# agv_drv.net
KiCad netlist of a schematic drawn in Altium Designer
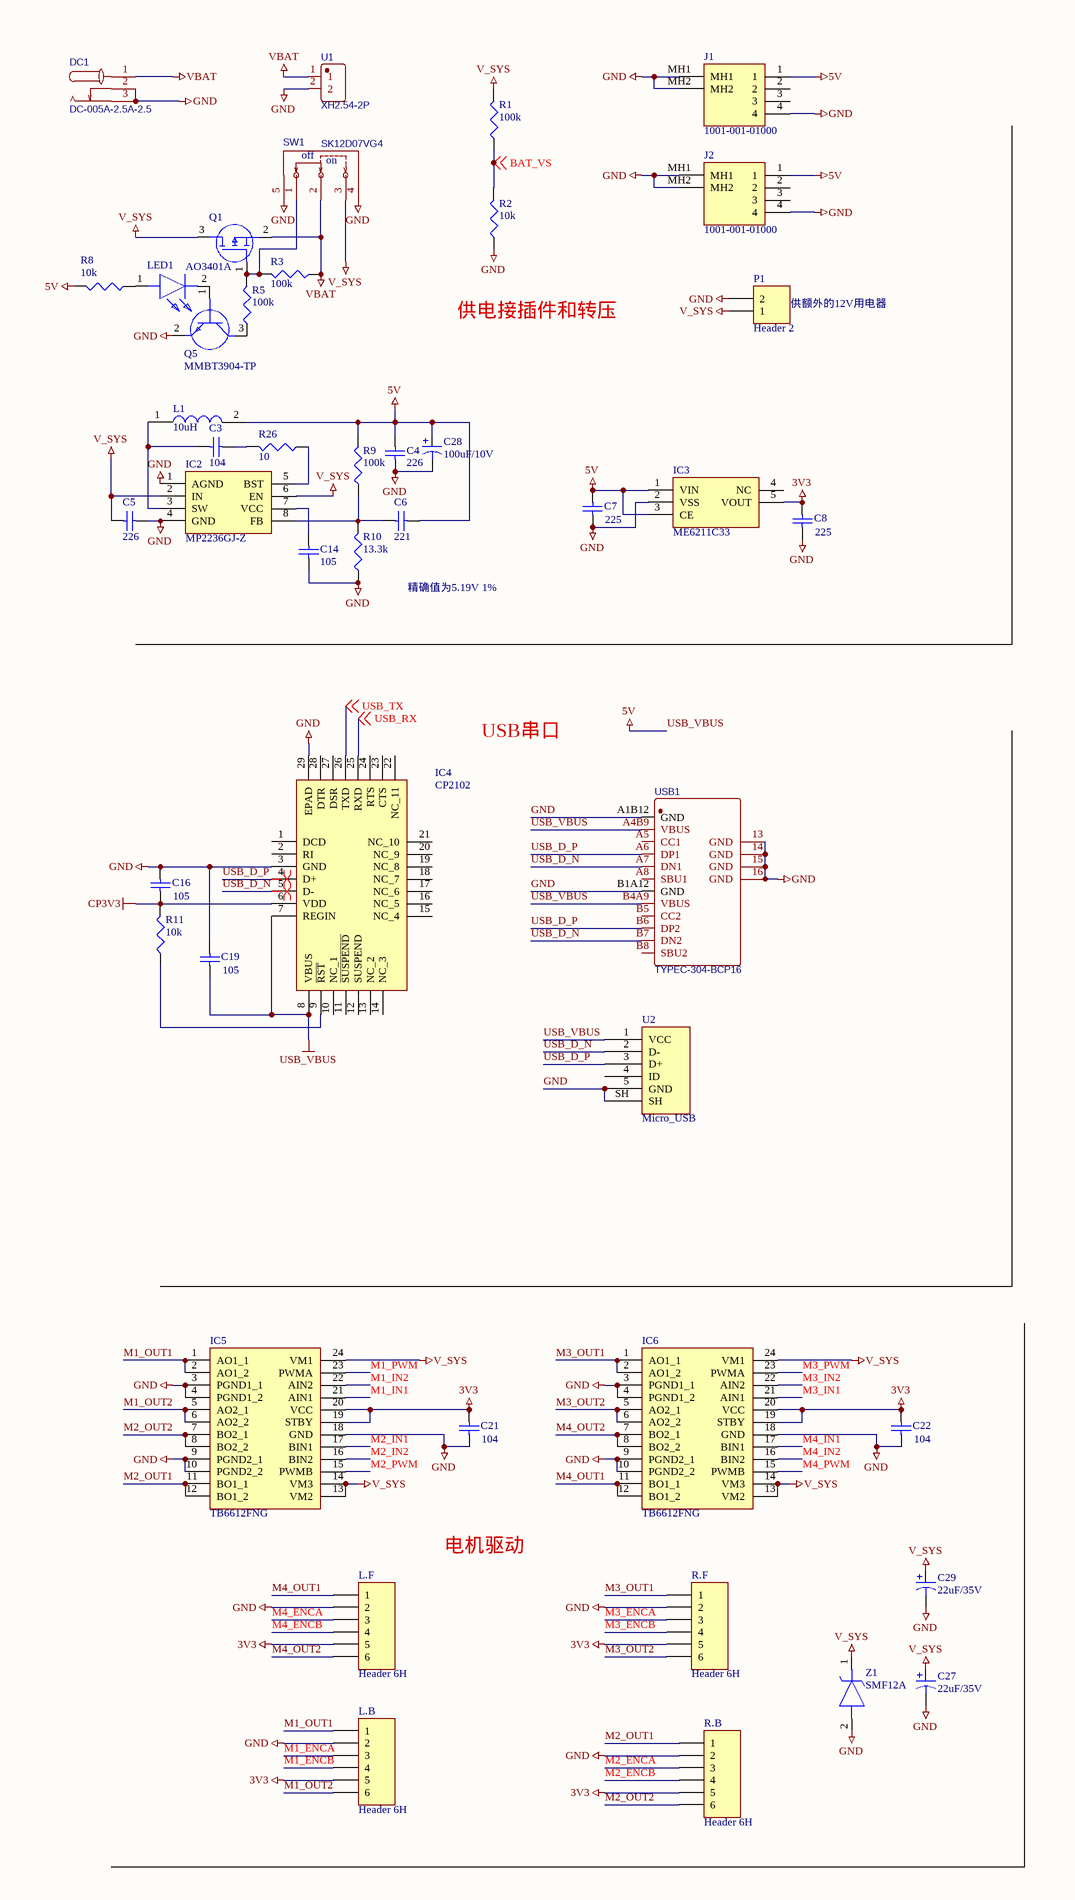
[diagram p0: agv_drv.SchDoc, left]
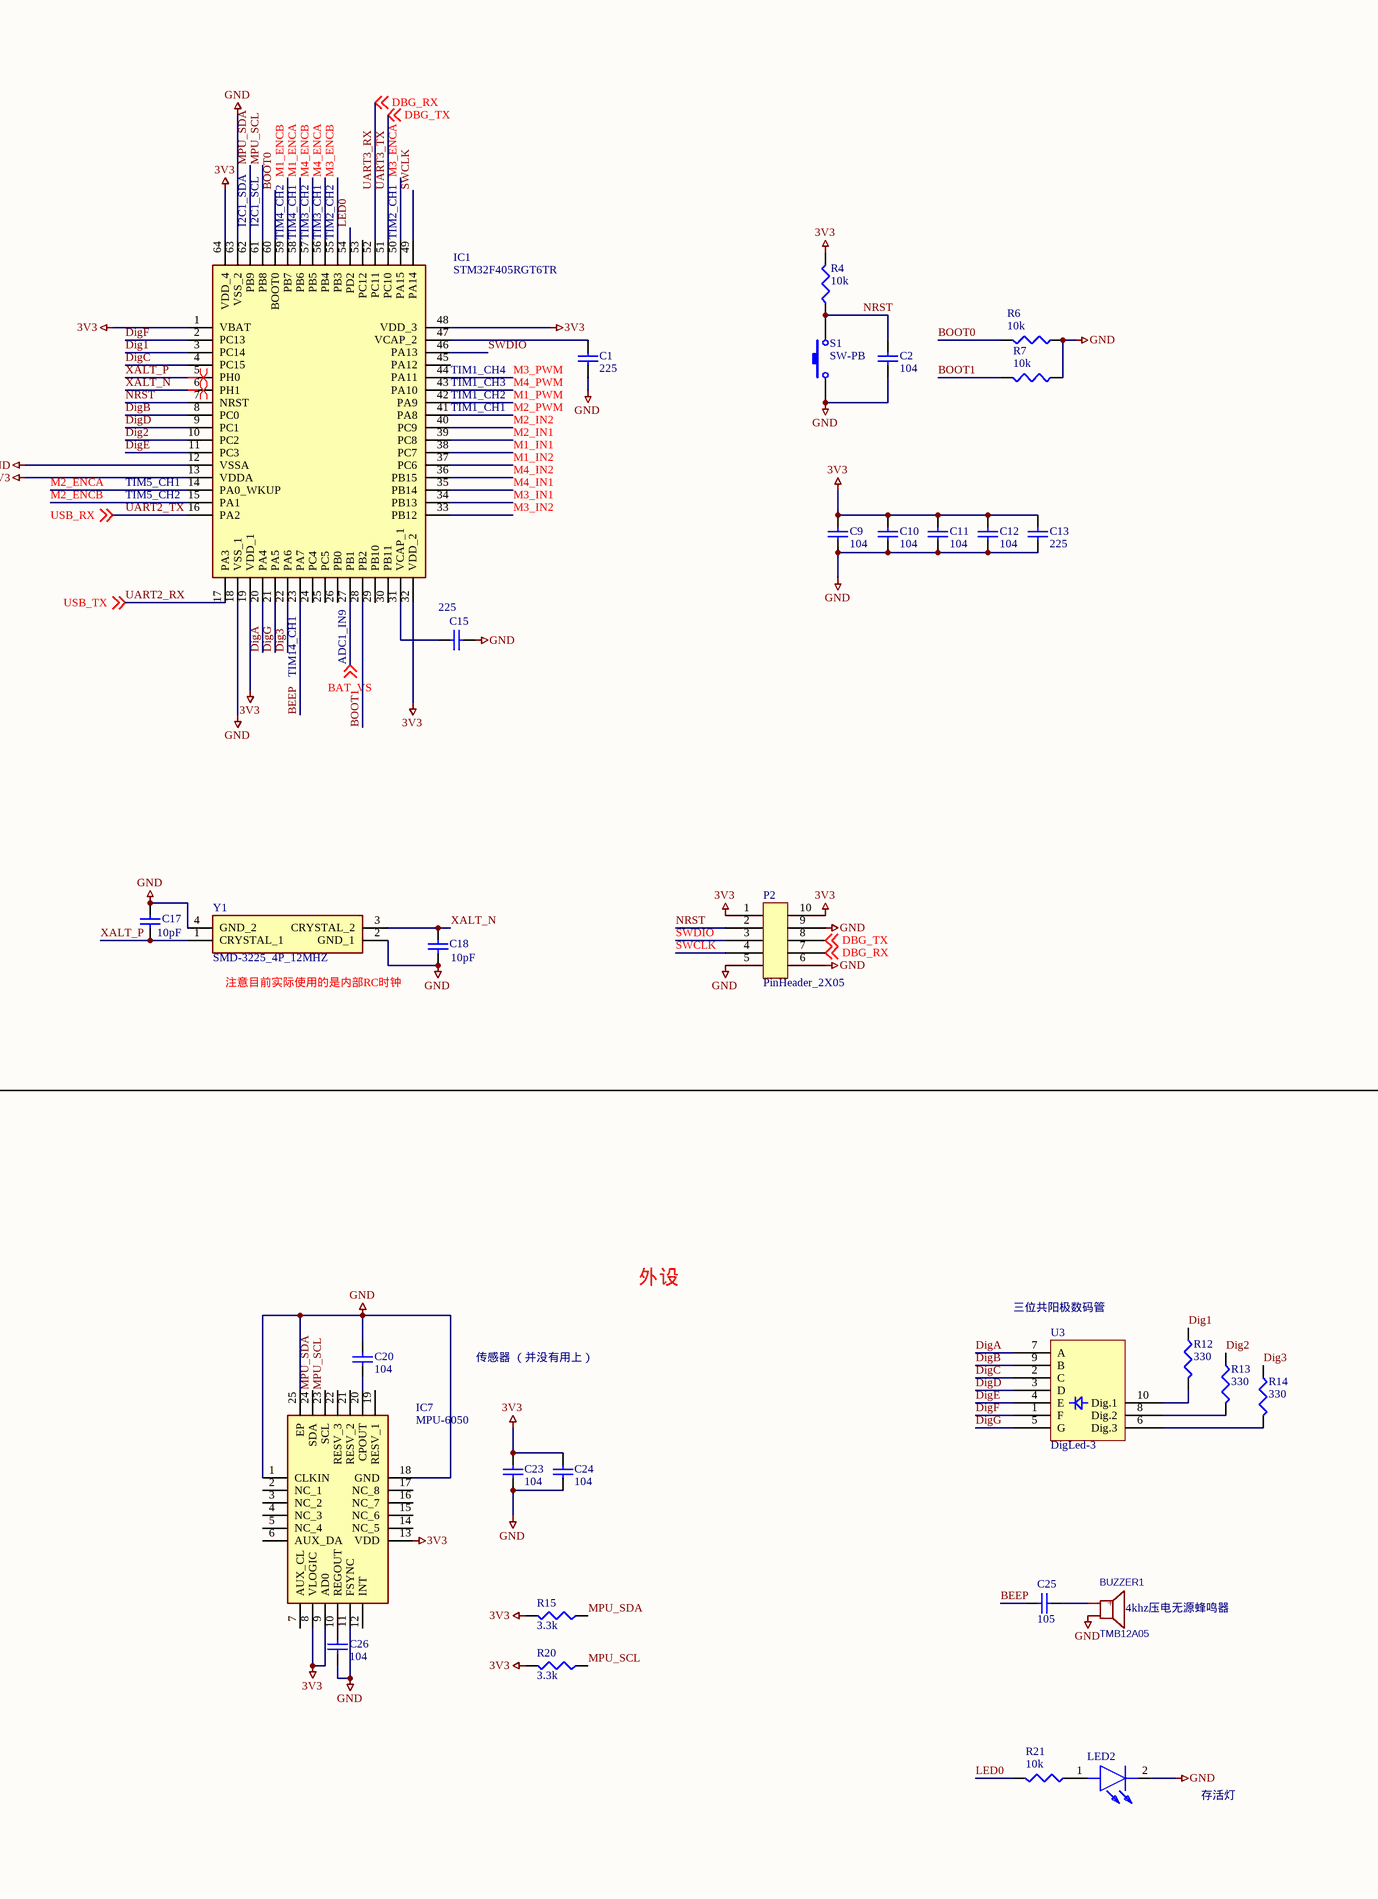
[diagram p1: agv_drv.SchDoc, right]

(export (version "E")
  (design (tool "Eeschema 10.0.6"))
  (components
    (comp (ref "BUZZER1")
      (value "TMB12A05")
      (footprint "BUZ-TH_BD12.5-P6.50-D0.8-FD")
      (fields (field (name "BOM_SUPPLIER PART") "C96093"))
      (libsource (lib "SamacSys") (part "TMB12A05"))
    )
    (comp (ref "C1")
      (value "225")
      (footprint "1608[0603]")
      (description "Capacitor (Semiconductor SIM Model)")
      (fields (field (name "PUBLISHER") "Altium Limited"))
      (libsource (lib "Miscellaneous Devices") (part "Cap Semi"))
    )
    (comp (ref "C2")
      (value "104")
      (footprint "1608[0603]")
      (description "Capacitor (Semiconductor SIM Model)")
      (fields (field (name "PUBLISHER") "Altium Limited"))
      (libsource (lib "Miscellaneous Devices") (part "Cap Semi"))
    )
    (comp (ref "C3")
      (value "104")
      (footprint "1608[0603]")
      (description "Capacitor (Semiconductor SIM Model)")
      (fields (field (name "PUBLISHER") "Altium Limited"))
      (libsource (lib "Miscellaneous Devices") (part "Cap Semi"))
    )
    (comp (ref "C4")
      (value "226")
      (footprint "C1206")
      (description "Capacitor (Semiconductor SIM Model)")
      (fields (field (name "PUBLISHER") "Altium Limited"))
      (libsource (lib "Miscellaneous Devices") (part "Cap Semi"))
    )
    (comp (ref "C5")
      (value "226")
      (footprint "C1206")
      (description "Capacitor (Semiconductor SIM Model)")
      (fields (field (name "PUBLISHER") "Altium Limited"))
      (libsource (lib "Miscellaneous Devices") (part "Cap Semi"))
    )
    (comp (ref "C6")
      (value "221")
      (footprint "1608[0603]")
      (description "Capacitor (Semiconductor SIM Model)")
      (fields (field (name "PUBLISHER") "Altium Limited"))
      (libsource (lib "Miscellaneous Devices") (part "Cap Semi"))
    )
    (comp (ref "C7")
      (value "225")
      (footprint "1608[0603]")
      (description "Capacitor (Semiconductor SIM Model)")
      (fields (field (name "PUBLISHER") "Altium Limited"))
      (libsource (lib "Miscellaneous Devices") (part "Cap Semi"))
    )
    (comp (ref "C8")
      (value "225")
      (footprint "1608[0603]")
      (description "Capacitor (Semiconductor SIM Model)")
      (fields (field (name "PUBLISHER") "Altium Limited"))
      (libsource (lib "Miscellaneous Devices") (part "Cap Semi"))
    )
    (comp (ref "C9")
      (value "104")
      (footprint "1608[0603]")
      (description "Capacitor (Semiconductor SIM Model)")
      (fields (field (name "PUBLISHER") "Altium Limited"))
      (libsource (lib "Miscellaneous Devices") (part "Cap Semi"))
    )
    (comp (ref "C10")
      (value "104")
      (footprint "1608[0603]")
      (description "Capacitor (Semiconductor SIM Model)")
      (fields (field (name "PUBLISHER") "Altium Limited"))
      (libsource (lib "Miscellaneous Devices") (part "Cap Semi"))
    )
    (comp (ref "C11")
      (value "104")
      (footprint "1608[0603]")
      (description "Capacitor (Semiconductor SIM Model)")
      (fields (field (name "PUBLISHER") "Altium Limited"))
      (libsource (lib "Miscellaneous Devices") (part "Cap Semi"))
    )
    (comp (ref "C12")
      (value "104")
      (footprint "1608[0603]")
      (description "Capacitor (Semiconductor SIM Model)")
      (fields (field (name "PUBLISHER") "Altium Limited"))
      (libsource (lib "Miscellaneous Devices") (part "Cap Semi"))
    )
    (comp (ref "C13")
      (value "225")
      (footprint "1608[0603]")
      (description "Capacitor (Semiconductor SIM Model)")
      (fields (field (name "PUBLISHER") "Altium Limited"))
      (libsource (lib "Miscellaneous Devices") (part "Cap Semi"))
    )
    (comp (ref "C14")
      (value "105")
      (footprint "1608[0603]")
      (description "Capacitor (Semiconductor SIM Model)")
      (fields (field (name "PUBLISHER") "Altium Limited"))
      (libsource (lib "Miscellaneous Devices") (part "Cap Semi"))
    )
    (comp (ref "C15")
      (value "225")
      (footprint "1608[0603]")
      (description "Capacitor (Semiconductor SIM Model)")
      (fields (field (name "PUBLISHER") "Altium Limited"))
      (libsource (lib "Miscellaneous Devices") (part "Cap Semi"))
    )
    (comp (ref "C16")
      (value "105")
      (footprint "1608[0603]")
      (description "Capacitor (Semiconductor SIM Model)")
      (fields (field (name "PUBLISHER") "Altium Limited"))
      (libsource (lib "Miscellaneous Devices") (part "Cap Semi"))
    )
    (comp (ref "C17")
      (value "10pF")
      (footprint "1608[0603]")
      (description "Capacitor (Semiconductor SIM Model)")
      (fields (field (name "PUBLISHER") "Altium Limited"))
      (libsource (lib "Miscellaneous Devices") (part "Cap Semi"))
    )
    (comp (ref "C18")
      (value "10pF")
      (footprint "1608[0603]")
      (description "Capacitor (Semiconductor SIM Model)")
      (fields (field (name "PUBLISHER") "Altium Limited"))
      (libsource (lib "Miscellaneous Devices") (part "Cap Semi"))
    )
    (comp (ref "C19")
      (value "105")
      (footprint "1608[0603]")
      (description "Capacitor (Semiconductor SIM Model)")
      (fields (field (name "PUBLISHER") "Altium Limited"))
      (libsource (lib "Miscellaneous Devices") (part "Cap Semi"))
    )
    (comp (ref "C20")
      (value "104")
      (footprint "1608[0603]")
      (description "Capacitor (Semiconductor SIM Model)")
      (fields (field (name "PUBLISHER") "Altium Limited"))
      (libsource (lib "Miscellaneous Devices") (part "Cap Semi"))
    )
    (comp (ref "C21")
      (value "104")
      (footprint "1608[0603]")
      (description "Capacitor (Semiconductor SIM Model)")
      (fields (field (name "PUBLISHER") "Altium Limited"))
      (libsource (lib "Miscellaneous Devices") (part "Cap Semi"))
    )
    (comp (ref "C22")
      (value "104")
      (footprint "1608[0603]")
      (description "Capacitor (Semiconductor SIM Model)")
      (fields (field (name "PUBLISHER") "Altium Limited"))
      (libsource (lib "Miscellaneous Devices") (part "Cap Semi"))
    )
    (comp (ref "C23")
      (value "104")
      (footprint "1608[0603]")
      (description "Capacitor (Semiconductor SIM Model)")
      (fields (field (name "PUBLISHER") "Altium Limited"))
      (libsource (lib "Miscellaneous Devices") (part "Cap Semi"))
    )
    (comp (ref "C24")
      (value "104")
      (footprint "1608[0603]")
      (description "Capacitor (Semiconductor SIM Model)")
      (fields (field (name "PUBLISHER") "Altium Limited"))
      (libsource (lib "Miscellaneous Devices") (part "Cap Semi"))
    )
    (comp (ref "C25")
      (value "105")
      (footprint "1608[0603]")
      (description "Capacitor (Semiconductor SIM Model)")
      (fields (field (name "PUBLISHER") "Altium Limited"))
      (libsource (lib "Miscellaneous Devices") (part "Cap Semi"))
    )
    (comp (ref "C26")
      (value "104")
      (footprint "1608[0603]")
      (description "Capacitor (Semiconductor SIM Model)")
      (fields (field (name "PUBLISHER") "Altium Limited"))
      (libsource (lib "Miscellaneous Devices") (part "Cap Semi"))
    )
    (comp (ref "C27")
      (value "22uF/35V")
      (footprint "CAPAE5550X54L")
      (description "Polarized Capacitor (Radial)")
      (fields (field (name "PUBLISHER") "Altium Limited"))
      (libsource (lib "Miscellaneous Devices") (part "Cap Pol1"))
    )
    (comp (ref "C28")
      (value "100uF/10V")
      (footprint "CAPAE5550X54L")
      (description "Polarized Capacitor (Radial)")
      (fields (field (name "PUBLISHER") "Altium Limited"))
      (libsource (lib "Miscellaneous Devices") (part "Cap Pol1"))
    )
    (comp (ref "C29")
      (value "22uF/35V")
      (footprint "CAPAE5550X54L")
      (description "Polarized Capacitor (Radial)")
      (fields (field (name "PUBLISHER") "Altium Limited"))
      (libsource (lib "Miscellaneous Devices") (part "Cap Pol1"))
    )
    (comp (ref "DC1")
      (value "DC-005A-2.5A-2.5")
      (footprint "DC-IN-TH_DC-005A-2.5A-2.5")
      (fields (field (name "BOM_SUPPLIER PART") "C480364") (field (name "CONTRIBUTOR") "LCSC"))
      (libsource (lib "SamacSys") (part "DC-005A-2.5A-2.5"))
    )
    (comp (ref "IC1")
      (value "STM32F405RGT6TR")
      (footprint "SamacSys:QFP50P1200X1200X160-64N")
      (description "Integrated Circuit")
      (fields (field (name "MOUSER PART NUMBER") "511-STM32F405RGT6TR"))
      (libsource (lib "*") (part "STM32F405RGT6TR"))
    )
    (comp (ref "IC2")
      (value "MP2236GJ-Z")
      (footprint "SamacSys:SOT65P280X100-8N")
      (description "Integrated Circuit")
      (fields (field (name "MOUSER PART NUMBER") "946-MP2236GJ-Z"))
      (libsource (lib "*") (part "MP2236GJ-Z"))
    )
    (comp (ref "IC3")
      (value "ME6211C33")
      (footprint "SamacSys:SOT95P282X145-5N")
      (description "Integrated Circuit")
      (fields (field (name "MANUFACTURER_PART_NUMBER") "ME6211C33M5G"))
      (libsource (lib "*") (part "ME6211C33M5G"))
    )
    (comp (ref "IC4")
      (value "CP2102")
      (footprint "SamacSys:QFN50P500X500X100-29N-D")
      (description "Integrated Circuit")
      (fields (field (name "MOUSER PART NUMBER") "634-CP2102"))
      (libsource (lib "SamacSys") (part "CP2102"))
    )
    (comp (ref "IC5")
      (value "TB6612FNG")
      (footprint "SamacSys:SOP65P760X160-24N")
      (description "Integrated Circuit")
      (libsource (lib "*") (part "TB6612FNG"))
    )
    (comp (ref "IC6")
      (value "TB6612FNG")
      (footprint "SamacSys:SOP65P760X160-24N")
      (description "Integrated Circuit")
      (libsource (lib "*") (part "TB6612FNG"))
    )
    (comp (ref "IC7")
      (value "MPU-6050")
      (footprint "SamacSys:QFN50P400X400X95-25N")
      (description "Integrated Circuit")
      (fields (field (name "MOUSER PART NUMBER") "410-MPU-6050"))
      (libsource (lib "*") (part "MPU-6050"))
    )
    (comp (ref "J1")
      (value "1001-001-01000")
      (footprint "SamacSys:100100101000")
      (description "Connector")
      (libsource (lib "*") (part "1001-001-01000"))
    )
    (comp (ref "J2")
      (value "1001-001-01000")
      (footprint "SamacSys:100100101000")
      (description "Connector")
      (libsource (lib "*") (part "1001-001-01000"))
    )
    (comp (ref "L.B")
      (value "Header 6H")
      (footprint "HDR2.0-LI-6P")
      (description "Header, 6-Pin, Right Angle")
      (fields (field (name "PUBLISHER") "Altium Limited"))
      (libsource (lib "Miscellaneous Connectors") (part "Header 6H"))
    )
    (comp (ref "L.F")
      (value "Header 6H")
      (footprint "HDR2.0-LI-6P")
      (description "Header, 6-Pin, Right Angle")
      (fields (field (name "PUBLISHER") "Altium Limited"))
      (libsource (lib "Miscellaneous Connectors") (part "Header 6H"))
    )
    (comp (ref "L1")
      (value "10uH")
      (footprint "SamacSys:INDPM7266X300N")
      (description "Inductor")
      (fields
        (field (name "MANUFACTURER_PART_NUMBER") "ASPI-0630HI-4R7M-T15")
        (field (name "MOUSER PART NUMBER") "815-ASPI0630HI4R7T15")
      )
      (libsource (lib "SamacSys") (part "ASPI-0630HI-4R7M-T15"))
    )
    (comp (ref "LED1")
      (value "LED0805")
      (footprint "SamacSys:LED0805")
      (description "LED")
      (fields
        (field (name "MANUFACTURER_PART_NUMBER") "17-21SURC/S530-A3/TR8")
        (field (name "MOUSER PART NUMBER") "638-1721SURCS530A3")
      )
      (libsource (lib "SamacSys") (part "LED"))
    )
    (comp (ref "LED2")
      (value "LED0805")
      (footprint "SamacSys:LED0805")
      (description "LED")
      (fields
        (field (name "MANUFACTURER_PART_NUMBER") "17-21SURC/S530-A3/TR8")
        (field (name "MOUSER PART NUMBER") "638-1721SURCS530A3")
      )
      (libsource (lib "SamacSys") (part "LED"))
    )
    (comp (ref "P1")
      (value "Header 2")
      (footprint "PinSocket_1X02_P5.00MM")
      (description "Header, 2-Pin")
      (fields (field (name "PUBLISHER") "Altium Limited"))
      (libsource (lib "Miscellaneous Connectors") (part "Header 2"))
    )
    (comp (ref "P2")
      (value "PinHeader_2X05")
      (footprint "SidePinHeader_2x05_P2.54mm")
      (libsource (lib "Connector_Pin") (part "PinHeader_2X05"))
    )
    (comp (ref "Q1")
      (value "AO3401A")
      (footprint "SamacSys:SOT95P280X125-3N")
      (description "MOSFET (P-Channel)")
      (libsource (lib "SamacSys") (part "AO3401A"))
    )
    (comp (ref "Q5")
      (value "MMBT3904-TP")
      (footprint "SamacSys:SOT95P280X125-3N")
      (description "Transistor BJT NPN")
      (fields (field (name "MOUSER PART NUMBER") "833-MMBT3904-TP"))
      (libsource (lib "SamacSys") (part "MMBT3904-TP"))
    )
    (comp (ref "R.B")
      (value "Header 6H")
      (footprint "HDR2.0-LI-6P")
      (description "Header, 6-Pin, Right Angle")
      (fields (field (name "PUBLISHER") "Altium Limited"))
      (libsource (lib "Miscellaneous Connectors") (part "Header 6H"))
    )
    (comp (ref "R.F")
      (value "Header 6H")
      (footprint "HDR2.0-LI-6P")
      (description "Header, 6-Pin, Right Angle")
      (fields (field (name "PUBLISHER") "Altium Limited"))
      (libsource (lib "Miscellaneous Connectors") (part "Header 6H"))
    )
    (comp (ref "R1")
      (value "100k")
      (footprint "J1-0603")
      (description "Resistor")
      (fields (field (name "PUBLISHER") "Altium Limited"))
      (libsource (lib "Miscellaneous Devices") (part "Res3"))
    )
    (comp (ref "R2")
      (value "10k")
      (footprint "J1-0603")
      (description "Resistor")
      (fields (field (name "PUBLISHER") "Altium Limited"))
      (libsource (lib "Miscellaneous Devices") (part "Res3"))
    )
    (comp (ref "R3")
      (value "100k")
      (footprint "J1-0603")
      (description "Resistor")
      (fields (field (name "PUBLISHER") "Altium Limited"))
      (libsource (lib "Miscellaneous Devices") (part "Res3"))
    )
    (comp (ref "R4")
      (value "10k")
      (footprint "J1-0603")
      (description "Resistor")
      (fields (field (name "PUBLISHER") "Altium Limited"))
      (libsource (lib "Miscellaneous Devices") (part "Res3"))
    )
    (comp (ref "R5")
      (value "100k")
      (footprint "J1-0603")
      (description "Resistor")
      (fields (field (name "PUBLISHER") "Altium Limited"))
      (libsource (lib "Miscellaneous Devices") (part "Res3"))
    )
    (comp (ref "R6")
      (value "10k")
      (footprint "J1-0603")
      (description "Resistor")
      (fields (field (name "PUBLISHER") "Altium Limited"))
      (libsource (lib "Miscellaneous Devices") (part "Res3"))
    )
    (comp (ref "R7")
      (value "10k")
      (footprint "J1-0603")
      (description "Resistor")
      (fields (field (name "PUBLISHER") "Altium Limited"))
      (libsource (lib "Miscellaneous Devices") (part "Res3"))
    )
    (comp (ref "R8")
      (value "10k")
      (footprint "J1-0603")
      (description "Resistor")
      (fields (field (name "PUBLISHER") "Altium Limited"))
      (libsource (lib "Miscellaneous Devices") (part "Res3"))
    )
    (comp (ref "R9")
      (value "100k")
      (footprint "J1-0603")
      (description "Resistor")
      (fields (field (name "PUBLISHER") "Altium Limited"))
      (libsource (lib "Miscellaneous Devices") (part "Res3"))
    )
    (comp (ref "R10")
      (value "13.3k")
      (footprint "J1-0603")
      (description "Resistor")
      (fields (field (name "PUBLISHER") "Altium Limited"))
      (libsource (lib "Miscellaneous Devices") (part "Res3"))
    )
    (comp (ref "R11")
      (value "10k")
      (footprint "J1-0603")
      (description "Resistor")
      (fields (field (name "PUBLISHER") "Altium Limited"))
      (libsource (lib "Miscellaneous Devices") (part "Res3"))
    )
    (comp (ref "R12")
      (value "330")
      (footprint "J1-0603")
      (description "Resistor")
      (fields (field (name "PUBLISHER") "Altium Limited"))
      (libsource (lib "Miscellaneous Devices") (part "Res3"))
    )
    (comp (ref "R13")
      (value "330")
      (footprint "J1-0603")
      (description "Resistor")
      (fields (field (name "PUBLISHER") "Altium Limited"))
      (libsource (lib "Miscellaneous Devices") (part "Res3"))
    )
    (comp (ref "R14")
      (value "330")
      (footprint "J1-0603")
      (description "Resistor")
      (fields (field (name "PUBLISHER") "Altium Limited"))
      (libsource (lib "Miscellaneous Devices") (part "Res3"))
    )
    (comp (ref "R15")
      (value "3.3k")
      (footprint "J1-0603")
      (description "Resistor")
      (fields (field (name "PUBLISHER") "Altium Limited"))
      (libsource (lib "Miscellaneous Devices") (part "Res3"))
    )
    (comp (ref "R20")
      (value "3.3k")
      (footprint "J1-0603")
      (description "Resistor")
      (fields (field (name "PUBLISHER") "Altium Limited"))
      (libsource (lib "Miscellaneous Devices") (part "Res3"))
    )
    (comp (ref "R21")
      (value "10k")
      (footprint "J1-0603")
      (description "Resistor")
      (fields (field (name "PUBLISHER") "Altium Limited"))
      (libsource (lib "Miscellaneous Devices") (part "Res3"))
    )
    (comp (ref "R26")
      (value "10")
      (footprint "J1-0603")
      (description "Resistor")
      (fields (field (name "PUBLISHER") "Altium Limited"))
      (libsource (lib "Miscellaneous Devices") (part "Res3"))
    )
    (comp (ref "S1")
      (value "SW-PB")
      (footprint "SW_PB2_A1")
      (description "Switch")
      (fields (field (name "PUBLISHER") "Altium Limited"))
      (libsource (lib "Miscellaneous Devices") (part "SW-PB"))
    )
    (comp (ref "SW1")
      (value "SK12D07VG4")
      (footprint "SW-TH_SK12D07VG4")
      (fields (field (name "BOM_SUPPLIER PART") "C393937") (field (name "CONTRIBUTOR") "LCSC"))
      (libsource (lib "SamacSys") (part "SK12D07VG4"))
    )
    (comp (ref "U1")
      (value "XH2.54-2P")
      (footprint "CONN-TH_XH2.54-2P")
      (fields
        (field (name "BOM_SUPPLIER PART") "C2888344")
        (field (name "BOM_MANUFACTURER PART") "XH2.54-2P立式座子")
        (field (name "CONTRIBUTOR") "LCSC")
      )
      (libsource (lib "SamacSys") (part "XH2.54-2P"))
    )
    (comp (ref "U2")
      (value "Micro_USB")
      (footprint "MicroUSB")
      (description "micro USB B型座子")
      (libsource (lib "Connector_Pin") (part "Micro_USB"))
    )
    (comp (ref "U3")
      (value "DigLed-3")
      (footprint "DigLed-3-0.25inch")
      (description "共阳极三位数码管")
      (libsource (lib "SamacSys") (part "DigLed-3"))
    )
    (comp (ref "USB1")
      (value "TYPEC-304-BCP16")
      (footprint "USB-C-SMD_TYPEC-304-BCP16")
      (fields (field (name "BOM_SUPPLIER PART") "C720629") (field (name "CONTRIBUTOR") "LCSC"))
      (libsource (lib "SamacSys") (part "TYPEC-304-BCP16"))
    )
    (comp (ref "Y1")
      (value "SMD-3225_4P_12MHZ")
      (footprint "SamacSys:SMD3225_4P12288MHZ12PF10PPM4085")
      (description "Crystal or Oscillator")
      (fields (field (name "MANUFACTURER_PART_NUMBER") "SMD-3225_4P 12.288MHZ 12PF 10PPM -40~+85℃"))
      (libsource (lib "*") (part "SMD-3225_4P_12.288MHZ_12PF_10PPM_-40~+85"))
    )
    (comp (ref "Z1")
      (value "SMF12A")
      (footprint "SamacSys:SODFL3718X108N")
      (description "Zener Diode")
      (fields
        (field (name "MANUFACTURER_PART_NUMBER") "SMF24A-E3-08")
        (field (name "MOUSER PART NUMBER") "78-SMF24A-E3-08")
      )
      (libsource (lib "*") (part "SMF24A-E3-08"))
    )
  )
  (nets
    (net (code "1") (name "/BEEP") (class "Default")
      (node (ref "C25") (pin "2") (pinfunction "2_2") (pintype "passive"))
      (node (ref "IC1") (pin "23") (pinfunction "PA7_23") (pintype "passive"))
    )
    (net (code "2") (name "/BOOT0") (class "Default")
      (node (ref "IC1") (pin "60") (pinfunction "BOOT0_60") (pintype "passive"))
      (node (ref "R6") (pin "2") (pinfunction "2_2") (pintype "passive"))
    )
    (net (code "3") (name "/BOOT1") (class "Default")
      (node (ref "IC1") (pin "28") (pinfunction "PB2_28") (pintype "passive"))
      (node (ref "R7") (pin "2") (pinfunction "2_2") (pintype "passive"))
    )
    (net (code "4") (name "/Dig1") (class "Default")
      (node (ref "IC1") (pin "3") (pinfunction "PC14_3") (pintype "passive"))
      (node (ref "R12") (pin "1") (pinfunction "1_1") (pintype "passive"))
    )
    (net (code "5") (name "/Dig2") (class "Default")
      (node (ref "IC1") (pin "10") (pinfunction "PC2_10") (pintype "passive"))
      (node (ref "R13") (pin "1") (pinfunction "1_1") (pintype "passive"))
    )
    (net (code "6") (name "/Dig3") (class "Default")
      (node (ref "IC1") (pin "22") (pinfunction "PA6_22") (pintype "passive"))
      (node (ref "R14") (pin "1") (pinfunction "1_1") (pintype "passive"))
    )
    (net (code "7") (name "/DigA") (class "Default")
      (node (ref "IC1") (pin "20") (pinfunction "PA4_20") (pintype "passive"))
      (node (ref "U3") (pin "7") (pinfunction "A_7") (pintype "passive"))
    )
    (net (code "8") (name "/DigB") (class "Default")
      (node (ref "IC1") (pin "8") (pinfunction "PC0_8") (pintype "passive"))
      (node (ref "U3") (pin "9") (pinfunction "B_9") (pintype "passive"))
    )
    (net (code "9") (name "/DigC") (class "Default")
      (node (ref "IC1") (pin "4") (pinfunction "PC15_4") (pintype "passive"))
      (node (ref "U3") (pin "2") (pinfunction "C_2") (pintype "passive"))
    )
    (net (code "10") (name "/DigD") (class "Default")
      (node (ref "IC1") (pin "9") (pinfunction "PC1_9") (pintype "passive"))
      (node (ref "U3") (pin "3") (pinfunction "D_3") (pintype "passive"))
    )
    (net (code "11") (name "/DigE") (class "Default")
      (node (ref "IC1") (pin "11") (pinfunction "PC3_11") (pintype "passive"))
      (node (ref "U3") (pin "4") (pinfunction "E_4") (pintype "passive"))
    )
    (net (code "12") (name "/DigF") (class "Default")
      (node (ref "IC1") (pin "2") (pinfunction "PC13_2") (pintype "passive"))
      (node (ref "U3") (pin "1") (pinfunction "F_1") (pintype "passive"))
    )
    (net (code "13") (name "/DigG") (class "Default")
      (node (ref "IC1") (pin "21") (pinfunction "PA5_21") (pintype "passive"))
      (node (ref "U3") (pin "5") (pinfunction "G_5") (pintype "passive"))
    )
    (net (code "14") (name "/LED0") (class "Default")
      (node (ref "IC1") (pin "54") (pinfunction "PD2_54") (pintype "passive"))
      (node (ref "R21") (pin "2") (pinfunction "2_2") (pintype "passive"))
    )
    (net (code "15") (name "/M1_ENCA") (class "Default")
      (node (ref "IC1") (pin "58") (pinfunction "PB6_58") (pintype "passive"))
      (node (ref "L.B") (pin "3") (pinfunction "3_3") (pintype "passive"))
    )
    (net (code "16") (name "/M1_ENCB") (class "Default")
      (node (ref "IC1") (pin "59") (pinfunction "PB7_59") (pintype "passive"))
      (node (ref "L.B") (pin "4") (pinfunction "4_4") (pintype "passive"))
    )
    (net (code "17") (name "/M1_IN1") (class "Default")
      (node (ref "IC1") (pin "38") (pinfunction "PC7_38") (pintype "passive"))
      (node (ref "IC5") (pin "21") (pinfunction "AIN1_21") (pintype "passive"))
    )
    (net (code "18") (name "/M1_IN2") (class "Default")
      (node (ref "IC1") (pin "37") (pinfunction "PC6_37") (pintype "passive"))
      (node (ref "IC5") (pin "22") (pinfunction "AIN2_22") (pintype "passive"))
    )
    (net (code "19") (name "/M1_OUT1") (class "Default")
      (node (ref "IC5") (pin "1") (pinfunction "AO1_1_1") (pintype "passive"))
      (node (ref "IC5") (pin "2") (pinfunction "AO1_2_2") (pintype "passive"))
      (node (ref "L.B") (pin "1") (pinfunction "1_1") (pintype "passive"))
    )
    (net (code "20") (name "/M1_OUT2") (class "Default")
      (node (ref "IC5") (pin "5") (pinfunction "AO2_1_5") (pintype "passive"))
      (node (ref "IC5") (pin "6") (pinfunction "AO2_2_6") (pintype "passive"))
      (node (ref "L.B") (pin "6") (pinfunction "6_6") (pintype "passive"))
    )
    (net (code "21") (name "/M1_PWM") (class "Default")
      (node (ref "IC1") (pin "42") (pinfunction "PA9_42") (pintype "passive"))
      (node (ref "IC5") (pin "23") (pinfunction "PWMA_23") (pintype "passive"))
    )
    (net (code "22") (name "/M2_ENCA") (class "Default")
      (node (ref "IC1") (pin "14") (pinfunction "PA0_WKUP_14") (pintype "passive"))
      (node (ref "R.B") (pin "3") (pinfunction "3_3") (pintype "passive"))
    )
    (net (code "23") (name "/M2_ENCB") (class "Default")
      (node (ref "IC1") (pin "15") (pinfunction "PA1_15") (pintype "passive"))
      (node (ref "R.B") (pin "4") (pinfunction "4_4") (pintype "passive"))
    )
    (net (code "24") (name "/M2_IN1") (class "Default")
      (node (ref "IC1") (pin "39") (pinfunction "PC8_39") (pintype "passive"))
      (node (ref "IC5") (pin "17") (pinfunction "BIN1_17") (pintype "passive"))
    )
    (net (code "25") (name "/M2_IN2") (class "Default")
      (node (ref "IC1") (pin "40") (pinfunction "PC9_40") (pintype "passive"))
      (node (ref "IC5") (pin "16") (pinfunction "BIN2_16") (pintype "passive"))
    )
    (net (code "26") (name "/M2_OUT1") (class "Default")
      (node (ref "IC5") (pin "11") (pinfunction "BO1_1_11") (pintype "passive"))
      (node (ref "IC5") (pin "12") (pinfunction "BO1_2_12") (pintype "passive"))
      (node (ref "R.B") (pin "1") (pinfunction "1_1") (pintype "passive"))
    )
    (net (code "27") (name "/M2_OUT2") (class "Default")
      (node (ref "IC5") (pin "7") (pinfunction "BO2_1_7") (pintype "passive"))
      (node (ref "IC5") (pin "8") (pinfunction "BO2_2_8") (pintype "passive"))
      (node (ref "R.B") (pin "6") (pinfunction "6_6") (pintype "passive"))
    )
    (net (code "28") (name "/M2_PWM") (class "Default")
      (node (ref "IC1") (pin "41") (pinfunction "PA8_41") (pintype "passive"))
      (node (ref "IC5") (pin "15") (pinfunction "PWMB_15") (pintype "passive"))
    )
    (net (code "29") (name "/M3_ENCA") (class "Default")
      (node (ref "IC1") (pin "50") (pinfunction "PA15_50") (pintype "passive"))
      (node (ref "R.F") (pin "3") (pinfunction "3_3") (pintype "passive"))
    )
    (net (code "30") (name "/M3_ENCB") (class "Default")
      (node (ref "IC1") (pin "55") (pinfunction "PB3_55") (pintype "passive"))
      (node (ref "R.F") (pin "4") (pinfunction "4_4") (pintype "passive"))
    )
    (net (code "31") (name "/M3_IN1") (class "Default")
      (node (ref "IC1") (pin "34") (pinfunction "PB13_34") (pintype "passive"))
      (node (ref "IC6") (pin "21") (pinfunction "AIN1_21") (pintype "passive"))
    )
    (net (code "32") (name "/M3_IN2") (class "Default")
      (node (ref "IC1") (pin "33") (pinfunction "PB12_33") (pintype "passive"))
      (node (ref "IC6") (pin "22") (pinfunction "AIN2_22") (pintype "passive"))
    )
    (net (code "33") (name "/M3_OUT1") (class "Default")
      (node (ref "IC6") (pin "1") (pinfunction "AO1_1_1") (pintype "passive"))
      (node (ref "IC6") (pin "2") (pinfunction "AO1_2_2") (pintype "passive"))
      (node (ref "R.F") (pin "1") (pinfunction "1_1") (pintype "passive"))
    )
    (net (code "34") (name "/M3_OUT2") (class "Default")
      (node (ref "IC6") (pin "5") (pinfunction "AO2_1_5") (pintype "passive"))
      (node (ref "IC6") (pin "6") (pinfunction "AO2_2_6") (pintype "passive"))
      (node (ref "R.F") (pin "6") (pinfunction "6_6") (pintype "passive"))
    )
    (net (code "35") (name "/M3_PWM") (class "Default")
      (node (ref "IC1") (pin "44") (pinfunction "PA11_44") (pintype "passive"))
      (node (ref "IC6") (pin "23") (pinfunction "PWMA_23") (pintype "passive"))
    )
    (net (code "36") (name "/M4_ENCA") (class "Default")
      (node (ref "IC1") (pin "56") (pinfunction "PB4_56") (pintype "passive"))
      (node (ref "L.F") (pin "3") (pinfunction "3_3") (pintype "passive"))
    )
    (net (code "37") (name "/M4_ENCB") (class "Default")
      (node (ref "IC1") (pin "57") (pinfunction "PB5_57") (pintype "passive"))
      (node (ref "L.F") (pin "4") (pinfunction "4_4") (pintype "passive"))
    )
    (net (code "38") (name "/M4_IN1") (class "Default")
      (node (ref "IC1") (pin "35") (pinfunction "PB14_35") (pintype "passive"))
      (node (ref "IC6") (pin "17") (pinfunction "BIN1_17") (pintype "passive"))
    )
    (net (code "39") (name "/M4_IN2") (class "Default")
      (node (ref "IC1") (pin "36") (pinfunction "PB15_36") (pintype "passive"))
      (node (ref "IC6") (pin "16") (pinfunction "BIN2_16") (pintype "passive"))
    )
    (net (code "40") (name "/M4_OUT1") (class "Default")
      (node (ref "IC6") (pin "11") (pinfunction "BO1_1_11") (pintype "passive"))
      (node (ref "IC6") (pin "12") (pinfunction "BO1_2_12") (pintype "passive"))
      (node (ref "L.F") (pin "1") (pinfunction "1_1") (pintype "passive"))
    )
    (net (code "41") (name "/M4_OUT2") (class "Default")
      (node (ref "IC6") (pin "7") (pinfunction "BO2_1_7") (pintype "passive"))
      (node (ref "IC6") (pin "8") (pinfunction "BO2_2_8") (pintype "passive"))
      (node (ref "L.F") (pin "6") (pinfunction "6_6") (pintype "passive"))
    )
    (net (code "42") (name "/M4_PWM") (class "Default")
      (node (ref "IC1") (pin "43") (pinfunction "PA10_43") (pintype "passive"))
      (node (ref "IC6") (pin "15") (pinfunction "PWMB_15") (pintype "passive"))
    )
    (net (code "43") (name "/MPU_SCL") (class "Default")
      (node (ref "IC1") (pin "61") (pinfunction "PB8_61") (pintype "passive"))
      (node (ref "IC7") (pin "23") (pinfunction "SCL_23") (pintype "passive"))
      (node (ref "R20") (pin "1") (pinfunction "1_1") (pintype "passive"))
    )
    (net (code "44") (name "/MPU_SDA") (class "Default")
      (node (ref "IC1") (pin "62") (pinfunction "PB9_62") (pintype "passive"))
      (node (ref "IC7") (pin "24") (pinfunction "SDA_24") (pintype "passive"))
      (node (ref "R15") (pin "1") (pinfunction "1_1") (pintype "passive"))
    )
    (net (code "45") (name "/NRST") (class "Default")
      (node (ref "C2") (pin "2") (pinfunction "2_2") (pintype "passive"))
      (node (ref "IC1") (pin "7") (pinfunction "NRST_7") (pintype "passive"))
      (node (ref "P2") (pin "2") (pintype "passive"))
      (node (ref "R4") (pin "1") (pinfunction "1_1") (pintype "passive"))
      (node (ref "S1") (pin "2") (pinfunction "2_2") (pintype "passive"))
    )
    (net (code "46") (name "/SWCLK") (class "Default")
      (node (ref "IC1") (pin "49") (pinfunction "PA14_49") (pintype "passive"))
      (node (ref "P2") (pin "4") (pintype "passive"))
    )
    (net (code "47") (name "/SWDIO") (class "Default")
      (node (ref "IC1") (pin "46") (pinfunction "PA13_46") (pintype "passive"))
      (node (ref "P2") (pin "3") (pintype "passive"))
    )
    (net (code "48") (name "/USB_D_N") (class "Default")
      (node (ref "IC4") (pin "5") (pinfunction "D-_5") (pintype "passive"))
      (node (ref "U2") (pin "2") (pinfunction "D-_2") (pintype "passive"))
      (node (ref "USB1") (pin "A7") (pinfunction "DN1_A7") (pintype "passive"))
      (node (ref "USB1") (pin "B7") (pinfunction "DN2_B7") (pintype "passive"))
    )
    (net (code "49") (name "/USB_D_P") (class "Default")
      (node (ref "IC4") (pin "4") (pinfunction "D+_4") (pintype "passive"))
      (node (ref "U2") (pin "3") (pinfunction "D+_3") (pintype "passive"))
      (node (ref "USB1") (pin "A6") (pinfunction "DP1_A6") (pintype "passive"))
      (node (ref "USB1") (pin "B6") (pinfunction "DP2_B6") (pintype "passive"))
    )
    (net (code "50") (name "/XALT_N") (class "Default")
      (node (ref "C18") (pin "2") (pinfunction "2_2") (pintype "passive"))
      (node (ref "IC1") (pin "6") (pinfunction "PH1_6") (pintype "passive"))
      (node (ref "Y1") (pin "3") (pinfunction "CRYSTAL_2_3") (pintype "passive"))
    )
    (net (code "51") (name "/XALT_P") (class "Default")
      (node (ref "C17") (pin "1") (pinfunction "1_1") (pintype "passive"))
      (node (ref "IC1") (pin "5") (pinfunction "PH0_5") (pintype "passive"))
      (node (ref "Y1") (pin "1") (pinfunction "CRYSTAL_1_1") (pintype "passive"))
    )
    (net (code "52") (name "3V3") (class "Default")
      (node (ref "C10") (pin "2") (pinfunction "2_2") (pintype "passive"))
      (node (ref "C11") (pin "2") (pinfunction "2_2") (pintype "passive"))
      (node (ref "C12") (pin "2") (pinfunction "2_2") (pintype "passive"))
      (node (ref "C13") (pin "2") (pinfunction "2_2") (pintype "passive"))
      (node (ref "C21") (pin "1") (pinfunction "1_1") (pintype "passive"))
      (node (ref "C22") (pin "1") (pinfunction "1_1") (pintype "passive"))
      (node (ref "C23") (pin "2") (pinfunction "2_2") (pintype "passive"))
      (node (ref "C24") (pin "2") (pinfunction "2_2") (pintype "passive"))
      (node (ref "C8") (pin "2") (pinfunction "2_2") (pintype "passive"))
      (node (ref "C9") (pin "2") (pinfunction "2_2") (pintype "passive"))
      (node (ref "IC1") (pin "1") (pinfunction "VBAT_1") (pintype "passive"))
      (node (ref "IC1") (pin "13") (pinfunction "VDDA_13") (pintype "passive"))
      (node (ref "IC1") (pin "19") (pinfunction "VDD_1_19") (pintype "passive"))
      (node (ref "IC1") (pin "32") (pinfunction "VDD_2_32") (pintype "passive"))
      (node (ref "IC1") (pin "48") (pinfunction "VDD_3_48") (pintype "passive"))
      (node (ref "IC1") (pin "64") (pinfunction "VDD_4_64") (pintype "passive"))
      (node (ref "IC3") (pin "5") (pinfunction "VOUT_5") (pintype "passive"))
      (node (ref "IC5") (pin "19") (pinfunction "STBY_19") (pintype "passive"))
      (node (ref "IC5") (pin "20") (pinfunction "VCC_20") (pintype "passive"))
      (node (ref "IC6") (pin "19") (pinfunction "STBY_19") (pintype "passive"))
      (node (ref "IC6") (pin "20") (pinfunction "VCC_20") (pintype "passive"))
      (node (ref "IC7") (pin "13") (pinfunction "VDD_13") (pintype "passive"))
      (node (ref "IC7") (pin "8") (pinfunction "VLOGIC_8") (pintype "passive"))
      (node (ref "IC7") (pin "9") (pinfunction "AD0_9") (pintype "passive"))
      (node (ref "L.B") (pin "5") (pinfunction "5_5") (pintype "passive"))
      (node (ref "L.F") (pin "5") (pinfunction "5_5") (pintype "passive"))
      (node (ref "P2") (pin "1") (pintype "passive"))
      (node (ref "P2") (pin "10") (pintype "passive"))
      (node (ref "R.B") (pin "5") (pinfunction "5_5") (pintype "passive"))
      (node (ref "R.F") (pin "5") (pinfunction "5_5") (pintype "passive"))
      (node (ref "R15") (pin "2") (pinfunction "2_2") (pintype "passive"))
      (node (ref "R20") (pin "2") (pinfunction "2_2") (pintype "passive"))
      (node (ref "R4") (pin "2") (pinfunction "2_2") (pintype "passive"))
    )
    (net (code "53") (name "5V") (class "Default")
      (node (ref "C19") (pin "1") (pinfunction "1_1") (pintype "passive"))
      (node (ref "C28") (pin "1") (pinfunction "1_1") (pintype "passive"))
      (node (ref "C4") (pin "2") (pinfunction "2_2") (pintype "passive"))
      (node (ref "C6") (pin "1") (pinfunction "1_1") (pintype "passive"))
      (node (ref "C7") (pin "2") (pinfunction "2_2") (pintype "passive"))
      (node (ref "IC3") (pin "1") (pinfunction "VIN_1") (pintype "passive"))
      (node (ref "IC3") (pin "3") (pinfunction "CE_3") (pintype "passive"))
      (node (ref "IC4") (pin "7") (pinfunction "REGIN_7") (pintype "passive"))
      (node (ref "IC4") (pin "8") (pinfunction "VBUS_8") (pintype "passive"))
      (node (ref "J1") (pin "1") (pinfunction "1_1") (pintype "passive"))
      (node (ref "J2") (pin "1") (pinfunction "1_1") (pintype "passive"))
      (node (ref "L1") (pin "2") (pinfunction "2_2") (pintype "passive"))
      (node (ref "R8") (pin "2") (pinfunction "2_2") (pintype "passive"))
      (node (ref "R9") (pin "2") (pinfunction "2_2") (pintype "passive"))
      (node (ref "U2") (pin "1") (pinfunction "VCC_1") (pintype "passive"))
      (node (ref "USB1") (pin "A4B9") (pinfunction "VBUS_A4B9") (pintype "passive"))
      (node (ref "USB1") (pin "B4A9") (pinfunction "VBUS_B4A9") (pintype "passive"))
    )
    (net (code "54") (name "BAT_VS") (class "Default")
      (node (ref "IC1") (pin "27") (pinfunction "PB1_27") (pintype "passive"))
      (node (ref "R1") (pin "1") (pinfunction "1_1") (pintype "passive"))
      (node (ref "R2") (pin "2") (pinfunction "2_2") (pintype "passive"))
    )
    (net (code "55") (name "CP3V3") (class "Default")
      (node (ref "C16") (pin "1") (pinfunction "1_1") (pintype "passive"))
      (node (ref "IC4") (pin "6") (pinfunction "VDD_6") (pintype "passive"))
      (node (ref "R11") (pin "2") (pinfunction "2_2") (pintype "passive"))
    )
    (net (code "56") (name "DBG_RX") (class "Default")
      (node (ref "IC1") (pin "52") (pinfunction "PC11_52") (pintype "passive"))
      (node (ref "P2") (pin "7") (pintype "passive"))
    )
    (net (code "57") (name "DBG_TX") (class "Default")
      (node (ref "IC1") (pin "51") (pinfunction "PC10_51") (pintype "passive"))
      (node (ref "P2") (pin "8") (pintype "passive"))
    )
    (net (code "58") (name "GND") (class "Default")
      (node (ref "BUZZER1") (pin "2") (pinfunction "2_2") (pintype "passive"))
      (node (ref "C1") (pin "2") (pinfunction "2_2") (pintype "passive"))
      (node (ref "C10") (pin "1") (pinfunction "1_1") (pintype "passive"))
      (node (ref "C11") (pin "1") (pinfunction "1_1") (pintype "passive"))
      (node (ref "C12") (pin "1") (pinfunction "1_1") (pintype "passive"))
      (node (ref "C13") (pin "1") (pinfunction "1_1") (pintype "passive"))
      (node (ref "C14") (pin "2") (pinfunction "2_2") (pintype "passive"))
      (node (ref "C15") (pin "2") (pinfunction "2_2") (pintype "passive"))
      (node (ref "C16") (pin "2") (pinfunction "2_2") (pintype "passive"))
      (node (ref "C17") (pin "2") (pinfunction "2_2") (pintype "passive"))
      (node (ref "C18") (pin "1") (pinfunction "1_1") (pintype "passive"))
      (node (ref "C19") (pin "2") (pinfunction "2_2") (pintype "passive"))
      (node (ref "C2") (pin "1") (pinfunction "1_1") (pintype "passive"))
      (node (ref "C20") (pin "2") (pinfunction "2_2") (pintype "passive"))
      (node (ref "C21") (pin "2") (pinfunction "2_2") (pintype "passive"))
      (node (ref "C22") (pin "2") (pinfunction "2_2") (pintype "passive"))
      (node (ref "C23") (pin "1") (pinfunction "1_1") (pintype "passive"))
      (node (ref "C24") (pin "1") (pinfunction "1_1") (pintype "passive"))
      (node (ref "C26") (pin "1") (pinfunction "1_1") (pintype "passive"))
      (node (ref "C27") (pin "2") (pinfunction "2_2") (pintype "passive"))
      (node (ref "C28") (pin "2") (pinfunction "2_2") (pintype "passive"))
      (node (ref "C29") (pin "2") (pinfunction "2_2") (pintype "passive"))
      (node (ref "C4") (pin "1") (pinfunction "1_1") (pintype "passive"))
      (node (ref "C5") (pin "1") (pinfunction "1_1") (pintype "passive"))
      (node (ref "C7") (pin "1") (pinfunction "1_1") (pintype "passive"))
      (node (ref "C8") (pin "1") (pinfunction "1_1") (pintype "passive"))
      (node (ref "C9") (pin "1") (pinfunction "1_1") (pintype "passive"))
      (node (ref "DC1") (pin "2") (pinfunction "2_2") (pintype "passive"))
      (node (ref "DC1") (pin "3") (pinfunction "3_3") (pintype "passive"))
      (node (ref "IC1") (pin "12") (pinfunction "VSSA_12") (pintype "passive"))
      (node (ref "IC1") (pin "18") (pinfunction "VSS_1_18") (pintype "passive"))
      (node (ref "IC1") (pin "63") (pinfunction "VSS_2_63") (pintype "passive"))
      (node (ref "IC2") (pin "1") (pinfunction "AGND_1") (pintype "passive"))
      (node (ref "IC2") (pin "4") (pinfunction "GND_4") (pintype "passive"))
      (node (ref "IC3") (pin "2") (pinfunction "VSS_2") (pintype "passive"))
      (node (ref "IC4") (pin "29") (pinfunction "EPAD_29") (pintype "passive"))
      (node (ref "IC4") (pin "3") (pinfunction "GND_3") (pintype "passive"))
      (node (ref "IC5") (pin "10") (pinfunction "PGND2_2_10") (pintype "passive"))
      (node (ref "IC5") (pin "18") (pinfunction "GND_18") (pintype "passive"))
      (node (ref "IC5") (pin "3") (pinfunction "PGND1_1_3") (pintype "passive"))
      (node (ref "IC5") (pin "4") (pinfunction "PGND1_2_4") (pintype "passive"))
      (node (ref "IC5") (pin "9") (pinfunction "PGND2_1_9") (pintype "passive"))
      (node (ref "IC6") (pin "10") (pinfunction "PGND2_2_10") (pintype "passive"))
      (node (ref "IC6") (pin "18") (pinfunction "GND_18") (pintype "passive"))
      (node (ref "IC6") (pin "3") (pinfunction "PGND1_1_3") (pintype "passive"))
      (node (ref "IC6") (pin "4") (pinfunction "PGND1_2_4") (pintype "passive"))
      (node (ref "IC6") (pin "9") (pinfunction "PGND2_1_9") (pintype "passive"))
      (node (ref "IC7") (pin "1") (pinfunction "CLKIN_1") (pintype "passive"))
      (node (ref "IC7") (pin "11") (pinfunction "FSYNC_11") (pintype "passive"))
      (node (ref "IC7") (pin "18") (pinfunction "GND_18") (pintype "passive"))
      (node (ref "IC7") (pin "25") (pinfunction "EP_25") (pintype "passive"))
      (node (ref "J1") (pin "4") (pinfunction "4_4") (pintype "passive"))
      (node (ref "J1") (pin "MH1") (pinfunction "MH1_MH1") (pintype "passive"))
      (node (ref "J1") (pin "MH2") (pinfunction "MH2_MH2") (pintype "passive"))
      (node (ref "J2") (pin "4") (pinfunction "4_4") (pintype "passive"))
      (node (ref "J2") (pin "MH1") (pinfunction "MH1_MH1") (pintype "passive"))
      (node (ref "J2") (pin "MH2") (pinfunction "MH2_MH2") (pintype "passive"))
      (node (ref "L.B") (pin "2") (pinfunction "2_2") (pintype "passive"))
      (node (ref "L.F") (pin "2") (pinfunction "2_2") (pintype "passive"))
      (node (ref "LED2") (pin "2") (pinfunction "K_2") (pintype "passive"))
      (node (ref "P1") (pin "2") (pinfunction "2_2") (pintype "passive"))
      (node (ref "P2") (pin "5") (pintype "passive"))
      (node (ref "P2") (pin "6") (pintype "passive"))
      (node (ref "P2") (pin "9") (pintype "passive"))
      (node (ref "Q5") (pin "2") (pinfunction "E_2") (pintype "passive"))
      (node (ref "R.B") (pin "2") (pinfunction "2_2") (pintype "passive"))
      (node (ref "R.F") (pin "2") (pinfunction "2_2") (pintype "passive"))
      (node (ref "R10") (pin "1") (pinfunction "1_1") (pintype "passive"))
      (node (ref "R2") (pin "1") (pinfunction "1_1") (pintype "passive"))
      (node (ref "R6") (pin "1") (pinfunction "1_1") (pintype "passive"))
      (node (ref "R7") (pin "1") (pinfunction "1_1") (pintype "passive"))
      (node (ref "S1") (pin "1") (pinfunction "1_1") (pintype "passive"))
      (node (ref "SW1") (pin "4") (pinfunction "4_4") (pintype "passive"))
      (node (ref "SW1") (pin "5") (pinfunction "5_5") (pintype "passive"))
      (node (ref "U1") (pin "2") (pinfunction "2_2") (pintype "passive"))
      (node (ref "U2") (pin "5") (pinfunction "GND_5") (pintype "passive"))
      (node (ref "U2") (pin "SH") (pinfunction "SH_SH") (pintype "passive"))
      (node (ref "USB1") (pin "13") (pinfunction "GND_13") (pintype "passive"))
      (node (ref "USB1") (pin "14") (pinfunction "GND_14") (pintype "passive"))
      (node (ref "USB1") (pin "15") (pinfunction "GND_15") (pintype "passive"))
      (node (ref "USB1") (pin "16") (pinfunction "GND_16") (pintype "passive"))
      (node (ref "USB1") (pin "A1B12") (pinfunction "GND_A1B12") (pintype "passive"))
      (node (ref "USB1") (pin "B1A12") (pinfunction "GND_B1A12") (pintype "passive"))
      (node (ref "Y1") (pin "2") (pinfunction "GND_1_2") (pintype "passive"))
      (node (ref "Y1") (pin "4") (pinfunction "GND_2_4") (pintype "passive"))
      (node (ref "Z1") (pin "2") (pinfunction "A_2") (pintype "passive"))
    )
    (net (code "59") (name "Net-(BUZZER1-+)") (class "Default")
      (node (ref "BUZZER1") (pin "1") (pinfunction "+_1") (pintype "passive"))
      (node (ref "C25") (pin "1") (pinfunction "1_1") (pintype "passive"))
    )
    (net (code "60") (name "Net-(C3-Pad2)") (class "Default")
      (node (ref "C3") (pin "2") (pinfunction "2_2") (pintype "passive"))
      (node (ref "R26") (pin "2") (pinfunction "2_2") (pintype "passive"))
    )
    (net (code "61") (name "Net-(IC1-VCAP_1)") (class "Default")
      (node (ref "C15") (pin "1") (pinfunction "1_1") (pintype "passive"))
      (node (ref "IC1") (pin "31") (pinfunction "VCAP_1_31") (pintype "passive"))
    )
    (net (code "62") (name "Net-(IC1-VCAP_2)") (class "Default")
      (node (ref "C1") (pin "1") (pinfunction "1_1") (pintype "passive"))
      (node (ref "IC1") (pin "47") (pinfunction "VCAP_2_47") (pintype "passive"))
    )
    (net (code "63") (name "Net-(IC2-BST)") (class "Default")
      (node (ref "IC2") (pin "5") (pinfunction "BST_5") (pintype "passive"))
      (node (ref "R26") (pin "1") (pinfunction "1_1") (pintype "passive"))
    )
    (net (code "64") (name "Net-(IC2-FB)") (class "Default")
      (node (ref "C6") (pin "2") (pinfunction "2_2") (pintype "passive"))
      (node (ref "IC2") (pin "8") (pinfunction "FB_8") (pintype "passive"))
      (node (ref "R10") (pin "2") (pinfunction "2_2") (pintype "passive"))
      (node (ref "R9") (pin "1") (pinfunction "1_1") (pintype "passive"))
    )
    (net (code "65") (name "Net-(IC2-SW)") (class "Default")
      (node (ref "C3") (pin "1") (pinfunction "1_1") (pintype "passive"))
      (node (ref "IC2") (pin "3") (pinfunction "SW_3") (pintype "passive"))
      (node (ref "L1") (pin "1") (pinfunction "1_1") (pintype "passive"))
    )
    (net (code "66") (name "Net-(IC2-VCC)") (class "Default")
      (node (ref "C14") (pin "1") (pinfunction "1_1") (pintype "passive"))
      (node (ref "IC2") (pin "7") (pinfunction "VCC_7") (pintype "passive"))
    )
    (net (code "67") (name "Net-(IC4-~{RST})") (class "Default")
      (node (ref "IC4") (pin "9") (pinfunction "~{RST}_9") (pintype "passive"))
      (node (ref "R11") (pin "1") (pinfunction "1_1") (pintype "passive"))
    )
    (net (code "68") (name "Net-(IC7-CPOUT)") (class "Default")
      (node (ref "C20") (pin "1") (pinfunction "1_1") (pintype "passive"))
      (node (ref "IC7") (pin "20") (pinfunction "CPOUT_20") (pintype "passive"))
    )
    (net (code "69") (name "Net-(IC7-REGOUT)") (class "Default")
      (node (ref "C26") (pin "2") (pinfunction "2_2") (pintype "passive"))
      (node (ref "IC7") (pin "10") (pinfunction "REGOUT_10") (pintype "passive"))
    )
    (net (code "70") (name "Net-(LED1-A)") (class "Default")
      (node (ref "LED1") (pin "1") (pinfunction "A_1") (pintype "passive"))
      (node (ref "R8") (pin "1") (pinfunction "1_1") (pintype "passive"))
    )
    (net (code "71") (name "Net-(LED1-K)") (class "Default")
      (node (ref "LED1") (pin "2") (pinfunction "K_2") (pintype "passive"))
      (node (ref "Q5") (pin "1") (pinfunction "B_1") (pintype "passive"))
    )
    (net (code "72") (name "Net-(LED2-A)") (class "Default")
      (node (ref "LED2") (pin "1") (pinfunction "A_1") (pintype "passive"))
      (node (ref "R21") (pin "1") (pinfunction "1_1") (pintype "passive"))
    )
    (net (code "73") (name "Net-(Q1-G)") (class "Default")
      (node (ref "Q1") (pin "1") (pinfunction "G_1") (pintype "passive"))
      (node (ref "R3") (pin "2") (pinfunction "2_2") (pintype "passive"))
      (node (ref "R5") (pin "2") (pinfunction "2_2") (pintype "passive"))
      (node (ref "SW1") (pin "1") (pinfunction "1_1") (pintype "passive"))
    )
    (net (code "74") (name "Net-(Q5-C)") (class "Default")
      (node (ref "Q5") (pin "3") (pinfunction "C_3") (pintype "passive"))
      (node (ref "R5") (pin "1") (pinfunction "1_1") (pintype "passive"))
    )
    (net (code "75") (name "Net-(U3-Dig.1)") (class "Default")
      (node (ref "R12") (pin "2") (pinfunction "2_2") (pintype "passive"))
      (node (ref "U3") (pin "10") (pinfunction "Dig.1_10") (pintype "passive"))
    )
    (net (code "76") (name "Net-(U3-Dig.2)") (class "Default")
      (node (ref "R13") (pin "2") (pinfunction "2_2") (pintype "passive"))
      (node (ref "U3") (pin "8") (pinfunction "Dig.2_8") (pintype "passive"))
    )
    (net (code "77") (name "Net-(U3-Dig.3)") (class "Default")
      (node (ref "R14") (pin "2") (pinfunction "2_2") (pintype "passive"))
      (node (ref "U3") (pin "6") (pinfunction "Dig.3_6") (pintype "passive"))
    )
    (net (code "78") (name "USB_RX") (class "Default")
      (node (ref "IC1") (pin "16") (pinfunction "PA2_16") (pintype "passive"))
      (node (ref "IC4") (pin "25") (pinfunction "RXD_25") (pintype "passive"))
    )
    (net (code "79") (name "USB_TX") (class "Default")
      (node (ref "IC1") (pin "17") (pinfunction "PA3_17") (pintype "passive"))
      (node (ref "IC4") (pin "26") (pinfunction "TXD_26") (pintype "passive"))
    )
    (net (code "80") (name "VBAT") (class "Default")
      (node (ref "DC1") (pin "1") (pinfunction "1_1") (pintype "passive"))
      (node (ref "Q1") (pin "2") (pinfunction "S_2") (pintype "passive"))
      (node (ref "R3") (pin "1") (pinfunction "1_1") (pintype "passive"))
      (node (ref "SW1") (pin "2") (pinfunction "2_2") (pintype "passive"))
      (node (ref "U1") (pin "1") (pinfunction "1_1") (pintype "passive"))
    )
    (net (code "81") (name "V_SYS") (class "Default")
      (node (ref "C27") (pin "1") (pinfunction "1_1") (pintype "passive"))
      (node (ref "C29") (pin "1") (pinfunction "1_1") (pintype "passive"))
      (node (ref "C5") (pin "2") (pinfunction "2_2") (pintype "passive"))
      (node (ref "IC2") (pin "2") (pinfunction "IN_2") (pintype "passive"))
      (node (ref "IC2") (pin "6") (pinfunction "EN_6") (pintype "passive"))
      (node (ref "IC5") (pin "13") (pinfunction "VM2_13") (pintype "passive"))
      (node (ref "IC5") (pin "14") (pinfunction "VM3_14") (pintype "passive"))
      (node (ref "IC5") (pin "24") (pinfunction "VM1_24") (pintype "passive"))
      (node (ref "IC6") (pin "13") (pinfunction "VM2_13") (pintype "passive"))
      (node (ref "IC6") (pin "14") (pinfunction "VM3_14") (pintype "passive"))
      (node (ref "IC6") (pin "24") (pinfunction "VM1_24") (pintype "passive"))
      (node (ref "P1") (pin "1") (pinfunction "1_1") (pintype "passive"))
      (node (ref "Q1") (pin "3") (pinfunction "D_3") (pintype "passive"))
      (node (ref "R1") (pin "2") (pinfunction "2_2") (pintype "passive"))
      (node (ref "SW1") (pin "3") (pinfunction "3_3") (pintype "passive"))
      (node (ref "Z1") (pin "1") (pinfunction "K_1") (pintype "passive"))
    )
    (net (code "82") (name "unconnected-(IC1-PA12-Pad45)") (class "Default")
      (node (ref "IC1") (pin "45") (pinfunction "PA12_45") (pintype "passive"))
    )
    (net (code "83") (name "unconnected-(IC1-PB0-Pad26)") (class "Default")
      (node (ref "IC1") (pin "26") (pinfunction "PB0_26") (pintype "passive"))
    )
    (net (code "84") (name "unconnected-(IC1-PB10-Pad29)") (class "Default")
      (node (ref "IC1") (pin "29") (pinfunction "PB10_29") (pintype "passive"))
    )
    (net (code "85") (name "unconnected-(IC1-PB11-Pad30)") (class "Default")
      (node (ref "IC1") (pin "30") (pinfunction "PB11_30") (pintype "passive"))
    )
    (net (code "86") (name "unconnected-(IC1-PC4-Pad24)") (class "Default")
      (node (ref "IC1") (pin "24") (pinfunction "PC4_24") (pintype "passive"))
    )
    (net (code "87") (name "unconnected-(IC1-PC5-Pad25)") (class "Default")
      (node (ref "IC1") (pin "25") (pinfunction "PC5_25") (pintype "passive"))
    )
    (net (code "88") (name "unconnected-(IC1-PC12-Pad53)") (class "Default")
      (node (ref "IC1") (pin "53") (pinfunction "PC12_53") (pintype "passive"))
    )
    (net (code "89") (name "unconnected-(IC3-NC-Pad4)") (class "Default")
      (node (ref "IC3") (pin "4") (pinfunction "NC_4") (pintype "passive"))
    )
    (net (code "90") (name "unconnected-(IC4-CTS-Pad23)") (class "Default")
      (node (ref "IC4") (pin "23") (pinfunction "CTS_23") (pintype "passive"))
    )
    (net (code "91") (name "unconnected-(IC4-DCD-Pad1)") (class "Default")
      (node (ref "IC4") (pin "1") (pinfunction "DCD_1") (pintype "passive"))
    )
    (net (code "92") (name "unconnected-(IC4-DSR-Pad27)") (class "Default")
      (node (ref "IC4") (pin "27") (pinfunction "DSR_27") (pintype "passive"))
    )
    (net (code "93") (name "unconnected-(IC4-DTR-Pad28)") (class "Default")
      (node (ref "IC4") (pin "28") (pinfunction "DTR_28") (pintype "passive"))
    )
    (net (code "94") (name "unconnected-(IC4-NC_1-Pad10)") (class "Default")
      (node (ref "IC4") (pin "10") (pinfunction "NC_1_10") (pintype "passive"))
    )
    (net (code "95") (name "unconnected-(IC4-NC_2-Pad13)") (class "Default")
      (node (ref "IC4") (pin "13") (pinfunction "NC_2_13") (pintype "passive"))
    )
    (net (code "96") (name "unconnected-(IC4-NC_3-Pad14)") (class "Default")
      (node (ref "IC4") (pin "14") (pinfunction "NC_3_14") (pintype "passive"))
    )
    (net (code "97") (name "unconnected-(IC4-NC_4-Pad15)") (class "Default")
      (node (ref "IC4") (pin "15") (pinfunction "NC_4_15") (pintype "passive"))
    )
    (net (code "98") (name "unconnected-(IC4-NC_5-Pad16)") (class "Default")
      (node (ref "IC4") (pin "16") (pinfunction "NC_5_16") (pintype "passive"))
    )
    (net (code "99") (name "unconnected-(IC4-NC_6-Pad17)") (class "Default")
      (node (ref "IC4") (pin "17") (pinfunction "NC_6_17") (pintype "passive"))
    )
    (net (code "100") (name "unconnected-(IC4-NC_7-Pad18)") (class "Default")
      (node (ref "IC4") (pin "18") (pinfunction "NC_7_18") (pintype "passive"))
    )
    (net (code "101") (name "unconnected-(IC4-NC_8-Pad19)") (class "Default")
      (node (ref "IC4") (pin "19") (pinfunction "NC_8_19") (pintype "passive"))
    )
    (net (code "102") (name "unconnected-(IC4-NC_9-Pad20)") (class "Default")
      (node (ref "IC4") (pin "20") (pinfunction "NC_9_20") (pintype "passive"))
    )
    (net (code "103") (name "unconnected-(IC4-NC_10-Pad21)") (class "Default")
      (node (ref "IC4") (pin "21") (pinfunction "NC_10_21") (pintype "passive"))
    )
    (net (code "104") (name "unconnected-(IC4-NC_11-Pad22)") (class "Default")
      (node (ref "IC4") (pin "22") (pinfunction "NC_11_22") (pintype "passive"))
    )
    (net (code "105") (name "unconnected-(IC4-RI-Pad2)") (class "Default")
      (node (ref "IC4") (pin "2") (pinfunction "RI_2") (pintype "passive"))
    )
    (net (code "106") (name "unconnected-(IC4-RTS-Pad24)") (class "Default")
      (node (ref "IC4") (pin "24") (pinfunction "RTS_24") (pintype "passive"))
    )
    (net (code "107") (name "unconnected-(IC4-SUSPEND-Pad12)") (class "Default")
      (node (ref "IC4") (pin "12") (pinfunction "SUSPEND_12") (pintype "passive"))
    )
    (net (code "108") (name "unconnected-(IC4-~{SUSPEND}-Pad11)") (class "Default")
      (node (ref "IC4") (pin "11") (pinfunction "~{SUSPEND}_11") (pintype "passive"))
    )
    (net (code "109") (name "unconnected-(IC7-AUX_CL-Pad7)") (class "Default")
      (node (ref "IC7") (pin "7") (pinfunction "AUX_CL_7") (pintype "passive"))
    )
    (net (code "110") (name "unconnected-(IC7-AUX_DA-Pad6)") (class "Default")
      (node (ref "IC7") (pin "6") (pinfunction "AUX_DA_6") (pintype "passive"))
    )
    (net (code "111") (name "unconnected-(IC7-INT-Pad12)") (class "Default")
      (node (ref "IC7") (pin "12") (pinfunction "INT_12") (pintype "passive"))
    )
    (net (code "112") (name "unconnected-(IC7-NC_1-Pad2)") (class "Default")
      (node (ref "IC7") (pin "2") (pinfunction "NC_1_2") (pintype "passive"))
    )
    (net (code "113") (name "unconnected-(IC7-NC_2-Pad3)") (class "Default")
      (node (ref "IC7") (pin "3") (pinfunction "NC_2_3") (pintype "passive"))
    )
    (net (code "114") (name "unconnected-(IC7-NC_3-Pad4)") (class "Default")
      (node (ref "IC7") (pin "4") (pinfunction "NC_3_4") (pintype "passive"))
    )
    (net (code "115") (name "unconnected-(IC7-NC_4-Pad5)") (class "Default")
      (node (ref "IC7") (pin "5") (pinfunction "NC_4_5") (pintype "passive"))
    )
    (net (code "116") (name "unconnected-(IC7-NC_5-Pad14)") (class "Default")
      (node (ref "IC7") (pin "14") (pinfunction "NC_5_14") (pintype "passive"))
    )
    (net (code "117") (name "unconnected-(IC7-NC_6-Pad15)") (class "Default")
      (node (ref "IC7") (pin "15") (pinfunction "NC_6_15") (pintype "passive"))
    )
    (net (code "118") (name "unconnected-(IC7-NC_7-Pad16)") (class "Default")
      (node (ref "IC7") (pin "16") (pinfunction "NC_7_16") (pintype "passive"))
    )
    (net (code "119") (name "unconnected-(IC7-NC_8-Pad17)") (class "Default")
      (node (ref "IC7") (pin "17") (pinfunction "NC_8_17") (pintype "passive"))
    )
    (net (code "120") (name "unconnected-(IC7-RESV_1-Pad19)") (class "Default")
      (node (ref "IC7") (pin "19") (pinfunction "RESV_1_19") (pintype "passive"))
    )
    (net (code "121") (name "unconnected-(IC7-RESV_2-Pad21)") (class "Default")
      (node (ref "IC7") (pin "21") (pinfunction "RESV_2_21") (pintype "passive"))
    )
    (net (code "122") (name "unconnected-(IC7-RESV_3-Pad22)") (class "Default")
      (node (ref "IC7") (pin "22") (pinfunction "RESV_3_22") (pintype "passive"))
    )
    (net (code "123") (name "unconnected-(J1-Pad2)") (class "Default")
      (node (ref "J1") (pin "2") (pinfunction "2_2") (pintype "passive"))
    )
    (net (code "124") (name "unconnected-(J1-Pad3)") (class "Default")
      (node (ref "J1") (pin "3") (pinfunction "3_3") (pintype "passive"))
    )
    (net (code "125") (name "unconnected-(J2-Pad2)") (class "Default")
      (node (ref "J2") (pin "2") (pinfunction "2_2") (pintype "passive"))
    )
    (net (code "126") (name "unconnected-(J2-Pad3)") (class "Default")
      (node (ref "J2") (pin "3") (pinfunction "3_3") (pintype "passive"))
    )
    (net (code "127") (name "unconnected-(U2-ID-Pad4)") (class "Default")
      (node (ref "U2") (pin "4") (pinfunction "ID_4") (pintype "passive"))
    )
    (net (code "128") (name "unconnected-(USB1-CC1-PadA5)") (class "Default")
      (node (ref "USB1") (pin "A5") (pinfunction "CC1_A5") (pintype "passive"))
    )
    (net (code "129") (name "unconnected-(USB1-CC2-PadB5)") (class "Default")
      (node (ref "USB1") (pin "B5") (pinfunction "CC2_B5") (pintype "passive"))
    )
    (net (code "130") (name "unconnected-(USB1-SBU1-PadA8)") (class "Default")
      (node (ref "USB1") (pin "A8") (pinfunction "SBU1_A8") (pintype "passive"))
    )
    (net (code "131") (name "unconnected-(USB1-SBU2-PadB8)") (class "Default")
      (node (ref "USB1") (pin "B8") (pinfunction "SBU2_B8") (pintype "passive"))
    )
  )
)
